# KMO_IO_MV9.net
KiCad netlist of a schematic drawn in EAGLE
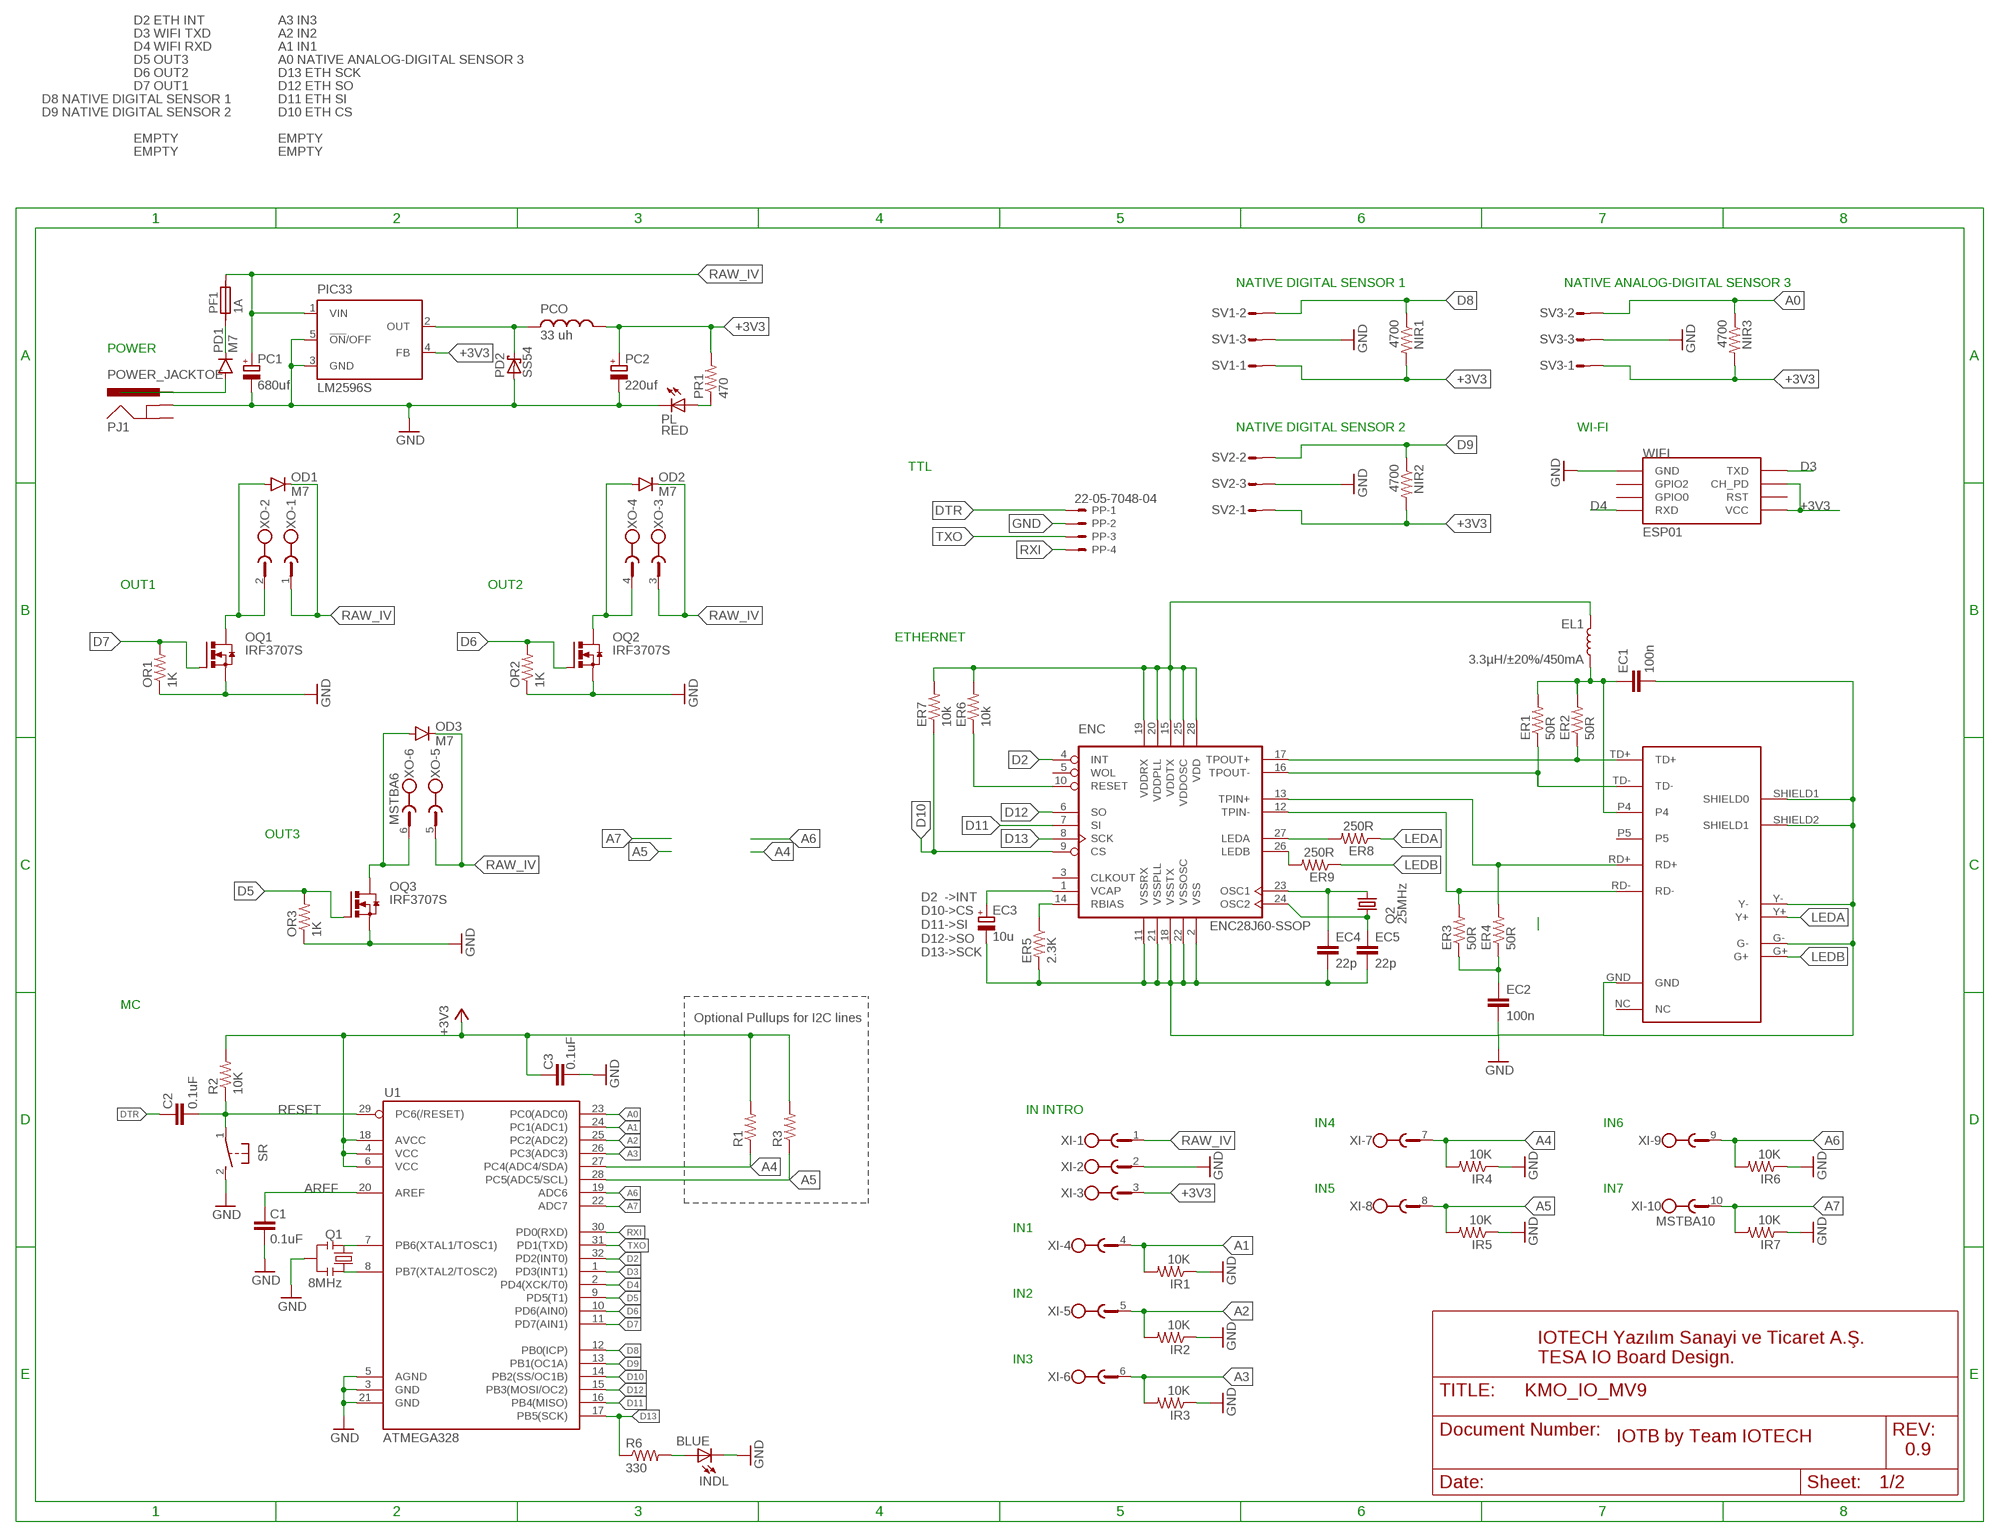
[diagram p0: schematic, sheet 1]
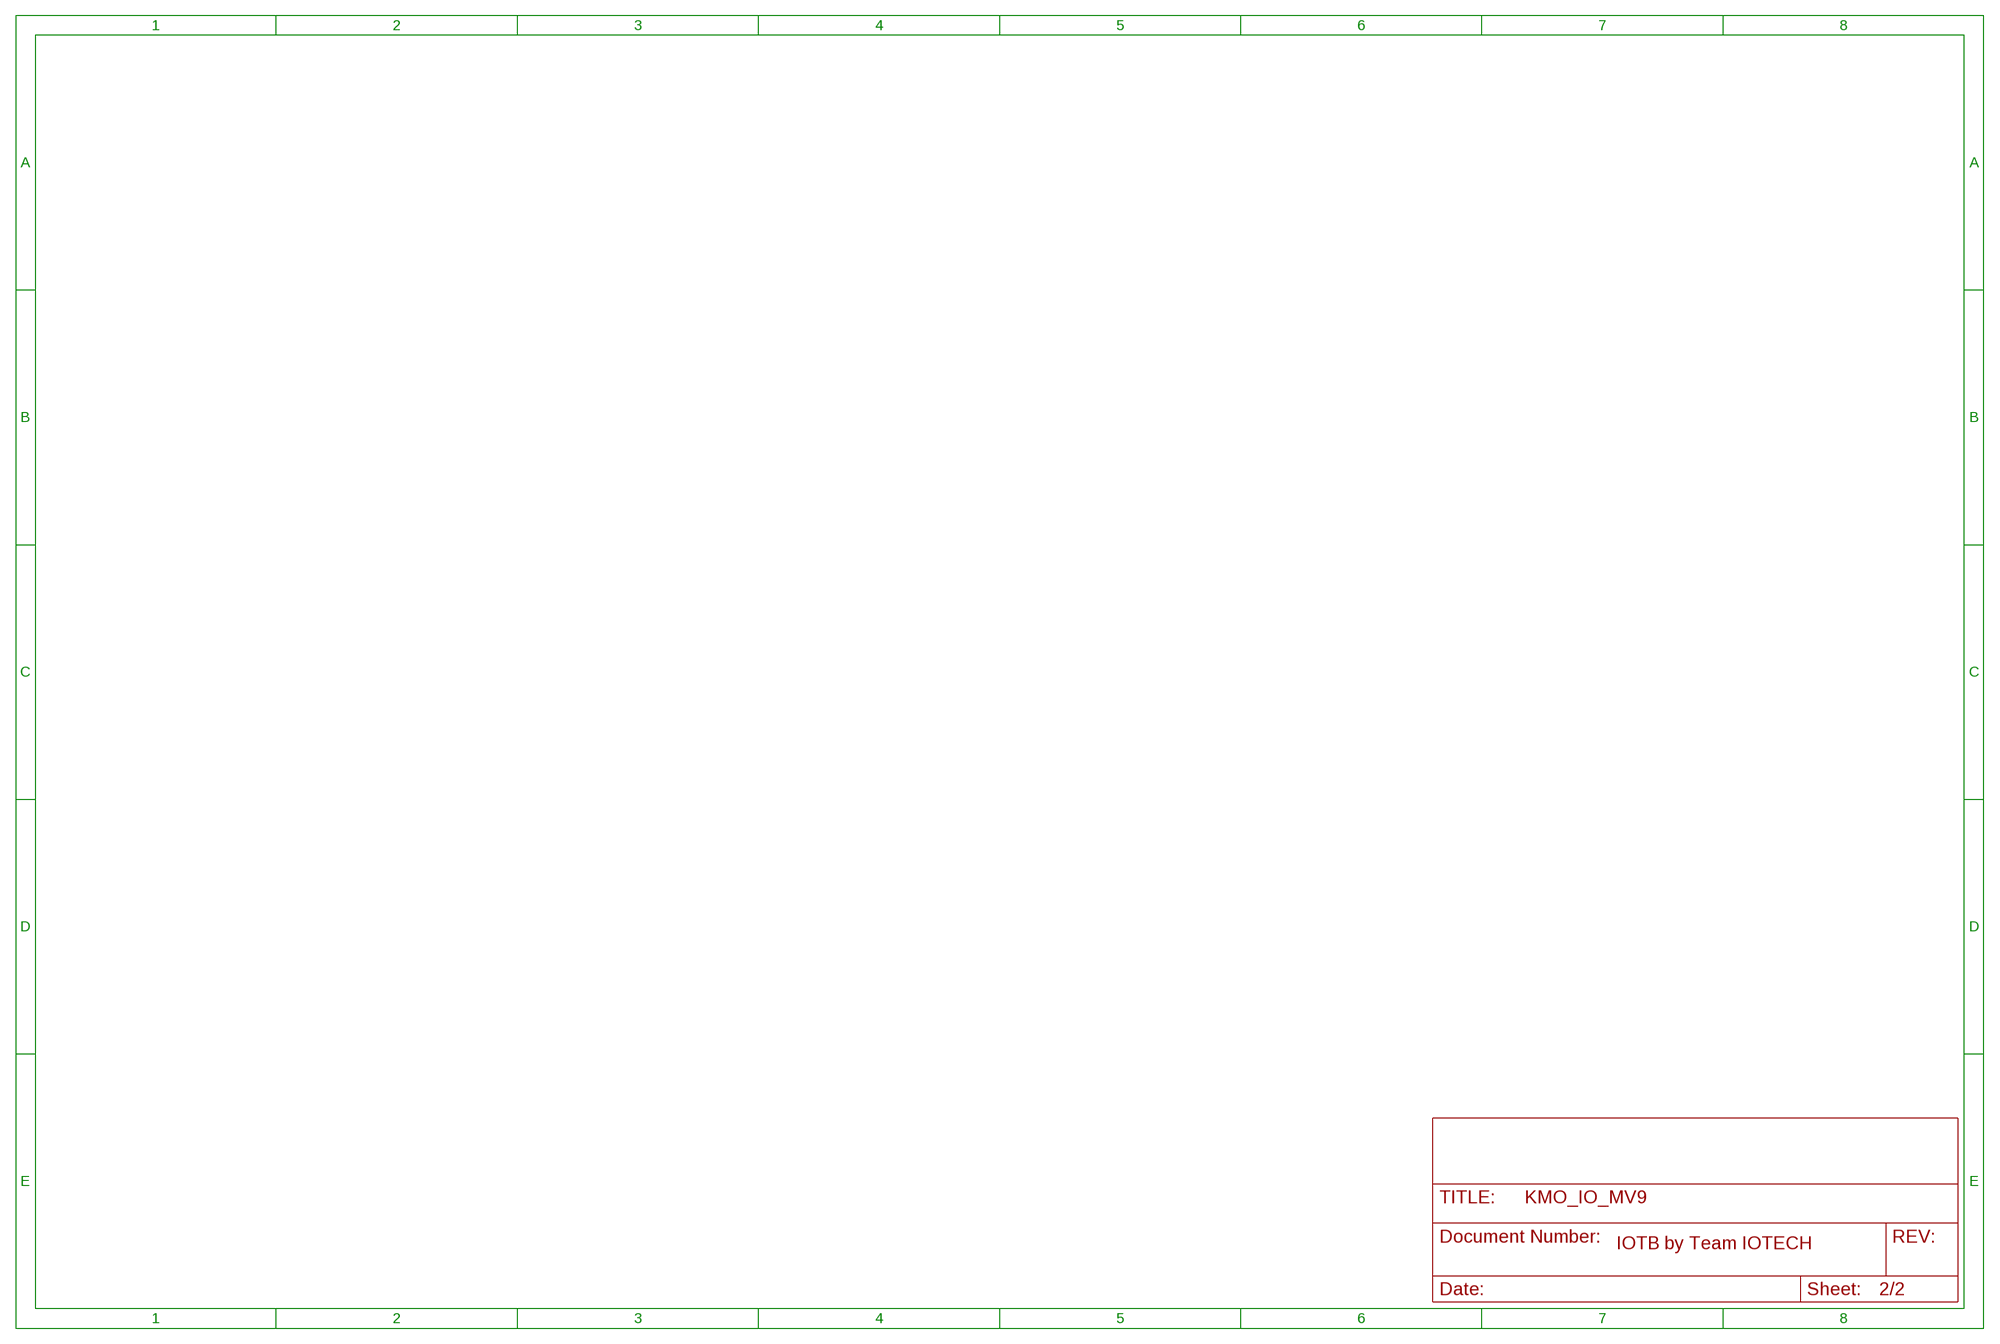
[diagram p1: schematic, sheet 2]

(export (version "E")
  (design (tool "Eeschema 10.0.6"))
  (components
    (comp (ref "C1")
      (value "0.1uF")
      (footprint "eagle-import:0805")
      (libsource (lib "eagle-import") (part "CAP0805"))
    )
    (comp (ref "C2")
      (value "0.1uF")
      (footprint "eagle-import:0805")
      (libsource (lib "eagle-import") (part "CAP0805"))
    )
    (comp (ref "C3")
      (value "0.1uF")
      (footprint "eagle-import:0805")
      (libsource (lib "eagle-import") (part "CAP0805"))
    )
    (comp (ref "EC1")
      (value "100n")
      (footprint "eagle-import:0805")
      (libsource (lib "eagle-import") (part "CAP0805"))
    )
    (comp (ref "EC2")
      (value "100n")
      (footprint "eagle-import:0805")
      (libsource (lib "eagle-import") (part "CAP0805"))
    )
    (comp (ref "EC3")
      (value "10u")
      (footprint "eagle-import:CT3216")
      (libsource (lib "eagle-import") (part "CPOL-EUCT3216"))
    )
    (comp (ref "EC4")
      (value "22p")
      (footprint "eagle-import:0805")
      (libsource (lib "eagle-import") (part "CAP0805"))
    )
    (comp (ref "EC5")
      (value "22p")
      (footprint "eagle-import:0805")
      (libsource (lib "eagle-import") (part "CAP0805"))
    )
    (comp (ref "EL1")
      (value "3.3µH/±20%/450mA")
      (footprint "eagle-import:0805")
      (libsource (lib "eagle-import") (part "INDUCTOR-0805-3.3UH"))
    )
    (comp (ref "ENC")
      (value "ENC28J60-SSOP")
      (footprint "eagle-import:SSOP28")
      (libsource (lib "eagle-import") (part "ENC28J60-SSOP"))
    )
    (comp (ref "ER1")
      (value "50R")
      (footprint "eagle-import:0805")
      (libsource (lib "eagle-import") (part "RESISTOR0805-RES"))
    )
    (comp (ref "ER2")
      (value "50R")
      (footprint "eagle-import:0805")
      (libsource (lib "eagle-import") (part "RESISTOR0805-RES"))
    )
    (comp (ref "ER3")
      (value "50R")
      (footprint "eagle-import:0805")
      (libsource (lib "eagle-import") (part "RESISTOR0805-RES"))
    )
    (comp (ref "ER4")
      (value "50R")
      (footprint "eagle-import:0805")
      (libsource (lib "eagle-import") (part "RESISTOR0805-RES"))
    )
    (comp (ref "ER5")
      (value "2.3K")
      (footprint "eagle-import:0805")
      (libsource (lib "eagle-import") (part "RESISTOR0805-RES"))
    )
    (comp (ref "ER6")
      (value "10k")
      (footprint "eagle-import:0805")
      (libsource (lib "eagle-import") (part "RESISTOR0805-RES"))
    )
    (comp (ref "ER7")
      (value "10k")
      (footprint "eagle-import:0805")
      (libsource (lib "eagle-import") (part "RESISTOR0805-RES"))
    )
    (comp (ref "ER8")
      (value "250R")
      (footprint "eagle-import:0805")
      (libsource (lib "eagle-import") (part "RESISTOR0805-RES"))
    )
    (comp (ref "ER9")
      (value "250R")
      (footprint "eagle-import:0805")
      (libsource (lib "eagle-import") (part "RESISTOR0805-RES"))
    )
    (comp (ref "INDL")
      (value "BLUE")
      (footprint "eagle-import:CHIP-LED0805")
      (libsource (lib "eagle-import") (part "LEDCHIP-LED0805"))
    )
    (comp (ref "IR1")
      (value "10K")
      (footprint "eagle-import:0805")
      (libsource (lib "eagle-import") (part "RESISTOR0805-RES"))
    )
    (comp (ref "IR2")
      (value "10K")
      (footprint "eagle-import:0805")
      (libsource (lib "eagle-import") (part "RESISTOR0805-RES"))
    )
    (comp (ref "IR3")
      (value "10K")
      (footprint "eagle-import:0805")
      (libsource (lib "eagle-import") (part "RESISTOR0805-RES"))
    )
    (comp (ref "IR4")
      (value "10K")
      (footprint "eagle-import:0805")
      (libsource (lib "eagle-import") (part "RESISTOR0805-RES"))
    )
    (comp (ref "IR5")
      (value "10K")
      (footprint "eagle-import:0805")
      (libsource (lib "eagle-import") (part "RESISTOR0805-RES"))
    )
    (comp (ref "IR6")
      (value "10K")
      (footprint "eagle-import:0805")
      (libsource (lib "eagle-import") (part "RESISTOR0805-RES"))
    )
    (comp (ref "IR7")
      (value "10K")
      (footprint "eagle-import:0805")
      (libsource (lib "eagle-import") (part "RESISTOR0805-RES"))
    )
    (comp (ref "NIR1")
      (value "4700")
      (footprint "eagle-import:0805")
      (libsource (lib "eagle-import") (part "RESISTOR0805-RES"))
    )
    (comp (ref "NIR2")
      (value "4700")
      (footprint "eagle-import:0805")
      (libsource (lib "eagle-import") (part "RESISTOR0805-RES"))
    )
    (comp (ref "NIR3")
      (value "4700")
      (footprint "eagle-import:0805")
      (libsource (lib "eagle-import") (part "RESISTOR0805-RES"))
    )
    (comp (ref "OD1")
      (value "M7")
      (footprint "eagle-import:SMA-DIODE")
      (libsource (lib "eagle-import") (part "DIODESMA"))
    )
    (comp (ref "OD2")
      (value "M7")
      (footprint "eagle-import:SMA-DIODE")
      (libsource (lib "eagle-import") (part "DIODESMA"))
    )
    (comp (ref "OD3")
      (value "M7")
      (footprint "eagle-import:SMA-DIODE")
      (libsource (lib "eagle-import") (part "DIODESMA"))
    )
    (comp (ref "OQ1")
      (value "IRF3707S")
      (footprint "eagle-import:D2PACK")
      (libsource (lib "eagle-import") (part "IRF3704S"))
    )
    (comp (ref "OQ2")
      (value "IRF3707S")
      (footprint "eagle-import:D2PACK")
      (libsource (lib "eagle-import") (part "IRF3704S"))
    )
    (comp (ref "OQ3")
      (value "IRF3707S")
      (footprint "eagle-import:D2PACK")
      (libsource (lib "eagle-import") (part "IRF3704S"))
    )
    (comp (ref "OR1")
      (value "1K")
      (footprint "eagle-import:0805")
      (libsource (lib "eagle-import") (part "RESISTOR0805-RES"))
    )
    (comp (ref "OR2")
      (value "1K")
      (footprint "eagle-import:0805")
      (libsource (lib "eagle-import") (part "RESISTOR0805-RES"))
    )
    (comp (ref "OR3")
      (value "1K")
      (footprint "eagle-import:0805")
      (libsource (lib "eagle-import") (part "RESISTOR0805-RES"))
    )
    (comp (ref "PC1")
      (value "680uf")
      (footprint "eagle-import:140CLH-1010")
      (libsource (lib "eagle-import") (part "CPOL-EU140CLH-1010"))
    )
    (comp (ref "PC2")
      (value "220uf")
      (footprint "eagle-import:140CLH-1010")
      (libsource (lib "eagle-import") (part "CPOL-EU140CLH-1010"))
    )
    (comp (ref "PCO")
      (value "33 uh")
      (footprint "eagle-import:MSS1260")
      (libsource (lib "eagle-import") (part "MSS1260"))
    )
    (comp (ref "PD1")
      (value "M7")
      (footprint "eagle-import:SMA-DIODE")
      (libsource (lib "eagle-import") (part "DIODESMA"))
    )
    (comp (ref "PD2")
      (value "SS54")
      (footprint "eagle-import:SMB")
      (libsource (lib "eagle-import") (part "SCHOTTKY-DIODESMD"))
    )
    (comp (ref "PF1")
      (value "1A")
      (footprint "eagle-import:1820")
      (libsource (lib "eagle-import") (part "SIBA194600"))
    )
    (comp (ref "PIC33")
      (value "LM2596S")
      (footprint "eagle-import:TO263-5")
      (fields (field (name "MF") "NATIONAL SEMICONDUCTOR") (field (name "MPN") "LM2596S-ADJ/NOPB"))
      (libsource (lib "eagle-import") (part "LM2596S"))
    )
    (comp (ref "PJ1")
      (value "POWER_JACKTOE")
      (footprint "eagle-import:POWER_JACK_SMD_OVERPASTE_TOE")
      (libsource (lib "eagle-import") (part "POWER_JACKTOE"))
    )
    (comp (ref "PL")
      (value "RED")
      (footprint "eagle-import:CHIP-LED0805")
      (libsource (lib "eagle-import") (part "LEDCHIP-LED0805"))
    )
    (comp (ref "PP")
      (value "22-05-7048-04")
      (footprint "eagle-import:7395-04")
      (fields (field (name "MF") "MOLEX"))
      (libsource (lib "eagle-import") (part "22-?-0405-7048"))
    )
    (comp (ref "PR1")
      (value "470")
      (footprint "eagle-import:0805")
      (libsource (lib "eagle-import") (part "RESISTOR0805-RES"))
    )
    (comp (ref "Q1")
      (value "8MHz")
      (footprint "eagle-import:RESONATOR-SMD-1_1")
      (libsource (lib "eagle-import") (part "RESONATOR1{colon}1"))
    )
    (comp (ref "Q2")
      (value "25MHz")
      (footprint "eagle-import:5.0X3.2_2")
      (libsource (lib "eagle-import") (part "KX-9B"))
    )
    (comp (ref "R1")
      (value "RESISTOR0805-RES")
      (footprint "eagle-import:0805")
      (libsource (lib "eagle-import") (part "RESISTOR0805-RES"))
    )
    (comp (ref "R2")
      (value "10K")
      (footprint "eagle-import:0805")
      (libsource (lib "eagle-import") (part "RESISTOR0805-RES"))
    )
    (comp (ref "R3")
      (value "RESISTOR0805-RES")
      (footprint "eagle-import:0805")
      (libsource (lib "eagle-import") (part "RESISTOR0805-RES"))
    )
    (comp (ref "R6")
      (value "330")
      (footprint "eagle-import:0805")
      (libsource (lib "eagle-import") (part "RESISTOR0805-RES"))
    )
    (comp (ref "SR")
      (value "31-XX")
      (footprint "eagle-import:B3F-31XX")
      (fields (field (name "MPN") "B3F-3100"))
      (libsource (lib "eagle-import") (part "31-XX"))
    )
    (comp (ref "SV1")
      (value "S03P")
      (footprint "eagle-import:S03P")
      (libsource (lib "eagle-import") (part "S03P"))
    )
    (comp (ref "SV2")
      (value "S03P")
      (footprint "eagle-import:S03P")
      (libsource (lib "eagle-import") (part "S03P"))
    )
    (comp (ref "SV3")
      (value "S03P")
      (footprint "eagle-import:S03P")
      (libsource (lib "eagle-import") (part "S03P"))
    )
    (comp (ref "U$2")
      (value "HR911105A")
      (footprint "eagle-import:RJ45")
      (libsource (lib "eagle-import") (part "HR911105A"))
    )
    (comp (ref "U1")
      (value "ATMEGA328")
      (footprint "eagle-import:TQFP32-08")
      (libsource (lib "eagle-import") (part "ATMEGA168"))
    )
    (comp (ref "WIFI")
      (value "ESP01")
      (footprint "eagle-import:ESP01")
      (libsource (lib "eagle-import") (part "ESP01"))
    )
    (comp (ref "XI")
      (value "MSTBA10")
      (footprint "eagle-import:MSTBA10")
      (fields (field (name "MF") "FARNELL") (field (name "MPN") "1757323"))
      (libsource (lib "eagle-import") (part "MSTBA10"))
    )
    (comp (ref "XO")
      (value "MSTBA6")
      (footprint "eagle-import:MSTBA6")
      (fields (field (name "MF") "FARNELL") (field (name "MPN") "1757284"))
      (libsource (lib "eagle-import") (part "MSTBA6"))
    )
  )
  (nets
    (net (code "1") (name "+3V3") (class "Default")
      (node (ref "C3") (pin "2") (pinfunction "2_2") (pintype "passive"))
      (node (ref "EL1") (pin "1") (pinfunction "1_1") (pintype "passive"))
      (node (ref "ENC") (pin "15") (pinfunction "VDDTX_15") (pintype "power_in"))
      (node (ref "ENC") (pin "19") (pinfunction "VDDRX_19") (pintype "power_in"))
      (node (ref "ENC") (pin "20") (pinfunction "VDDPLL_20") (pintype "power_in"))
      (node (ref "ENC") (pin "25") (pinfunction "VDDOSC_25") (pintype "power_in"))
      (node (ref "ENC") (pin "28") (pinfunction "VDD_28") (pintype "power_in"))
      (node (ref "ER6") (pin "2") (pinfunction "2_2") (pintype "passive"))
      (node (ref "ER7") (pin "2") (pinfunction "2_2") (pintype "passive"))
      (node (ref "NIR1") (pin "2") (pinfunction "2_2") (pintype "passive"))
      (node (ref "NIR2") (pin "2") (pinfunction "2_2") (pintype "passive"))
      (node (ref "NIR3") (pin "2") (pinfunction "2_2") (pintype "passive"))
      (node (ref "PC2") (pin "+") (pinfunction "+_+") (pintype "passive"))
      (node (ref "PCO") (pin "P$1") (pinfunction "P$1_P$1") (pintype "passive"))
      (node (ref "PIC33") (pin "4") (pinfunction "FB_4") (pintype "input"))
      (node (ref "PR1") (pin "2") (pinfunction "2_2") (pintype "passive"))
      (node (ref "R1") (pin "2") (pinfunction "2_2") (pintype "passive"))
      (node (ref "R2") (pin "2") (pinfunction "2_2") (pintype "passive"))
      (node (ref "R3") (pin "2") (pinfunction "2_2") (pintype "passive"))
      (node (ref "SV1") (pin "1") (pinfunction "S_1") (pintype "passive"))
      (node (ref "SV2") (pin "1") (pinfunction "S_1") (pintype "passive"))
      (node (ref "SV3") (pin "1") (pinfunction "S_1") (pintype "passive"))
      (node (ref "U1") (pin "18") (pinfunction "AVCC_18") (pintype "bidirectional"))
      (node (ref "U1") (pin "4") (pinfunction "VCC_4") (pintype "bidirectional"))
      (node (ref "U1") (pin "6") (pinfunction "VCC_6") (pintype "bidirectional"))
      (node (ref "WIFI") (pin "CH_PD") (pinfunction "CH_PD_CH_PD") (pintype "bidirectional"))
      (node (ref "WIFI") (pin "VCC") (pinfunction "VCC_VCC") (pintype "bidirectional"))
      (node (ref "XI") (pin "3") (pinfunction "1_3") (pintype "passive"))
    )
    (net (code "2") (name "A0") (class "Default")
      (node (ref "NIR3") (pin "1") (pinfunction "1_1") (pintype "passive"))
      (node (ref "SV3") (pin "2") (pinfunction "S_2") (pintype "passive"))
      (node (ref "U1") (pin "23") (pinfunction "PC0(ADC0)_23") (pintype "bidirectional"))
    )
    (net (code "3") (name "A1") (class "Default")
      (node (ref "IR1") (pin "2") (pinfunction "2_2") (pintype "passive"))
      (node (ref "U1") (pin "24") (pinfunction "PC1(ADC1)_24") (pintype "bidirectional"))
      (node (ref "XI") (pin "4") (pinfunction "1_4") (pintype "passive"))
    )
    (net (code "4") (name "A2") (class "Default")
      (node (ref "IR2") (pin "2") (pinfunction "2_2") (pintype "passive"))
      (node (ref "U1") (pin "25") (pinfunction "PC2(ADC2)_25") (pintype "bidirectional"))
      (node (ref "XI") (pin "5") (pinfunction "1_5") (pintype "passive"))
    )
    (net (code "5") (name "A3") (class "Default")
      (node (ref "IR3") (pin "2") (pinfunction "2_2") (pintype "passive"))
      (node (ref "U1") (pin "26") (pinfunction "PC3(ADC3)_26") (pintype "bidirectional"))
      (node (ref "XI") (pin "6") (pinfunction "1_6") (pintype "passive"))
    )
    (net (code "6") (name "A4") (class "Default")
      (node (ref "IR4") (pin "2") (pinfunction "2_2") (pintype "passive"))
      (node (ref "R1") (pin "1") (pinfunction "1_1") (pintype "passive"))
      (node (ref "U1") (pin "27") (pinfunction "PC4(ADC4/SDA)_27") (pintype "bidirectional"))
      (node (ref "XI") (pin "7") (pinfunction "1_7") (pintype "passive"))
    )
    (net (code "7") (name "A5") (class "Default")
      (node (ref "IR5") (pin "2") (pinfunction "2_2") (pintype "passive"))
      (node (ref "R3") (pin "1") (pinfunction "1_1") (pintype "passive"))
      (node (ref "U1") (pin "28") (pinfunction "PC5(ADC5/SCL)_28") (pintype "bidirectional"))
      (node (ref "XI") (pin "8") (pinfunction "1_8") (pintype "passive"))
    )
    (net (code "8") (name "A6") (class "Default")
      (node (ref "IR6") (pin "2") (pinfunction "2_2") (pintype "passive"))
      (node (ref "U1") (pin "19") (pinfunction "ADC6_19") (pintype "bidirectional"))
      (node (ref "XI") (pin "9") (pinfunction "1_9") (pintype "passive"))
    )
    (net (code "9") (name "A7") (class "Default")
      (node (ref "IR7") (pin "2") (pinfunction "2_2") (pintype "passive"))
      (node (ref "U1") (pin "22") (pinfunction "ADC7_22") (pintype "bidirectional"))
      (node (ref "XI") (pin "10") (pinfunction "1_10") (pintype "passive"))
    )
    (net (code "10") (name "AREF") (class "Default")
      (node (ref "C1") (pin "2") (pinfunction "2_2") (pintype "passive"))
      (node (ref "U1") (pin "20") (pinfunction "AREF_20") (pintype "bidirectional"))
    )
    (net (code "11") (name "D2") (class "Default")
      (node (ref "ENC") (pin "4") (pinfunction "INT_4") (pintype "output"))
      (node (ref "U1") (pin "32") (pinfunction "PD2(INT0)_32") (pintype "bidirectional"))
    )
    (net (code "12") (name "D3") (class "Default")
      (node (ref "U1") (pin "1") (pinfunction "PD3(INT1)_1") (pintype "bidirectional"))
      (node (ref "WIFI") (pin "TX") (pinfunction "TXD_TX") (pintype "bidirectional"))
    )
    (net (code "13") (name "D4") (class "Default")
      (node (ref "U1") (pin "2") (pinfunction "PD4(XCK/T0)_2") (pintype "bidirectional"))
      (node (ref "WIFI") (pin "RX") (pinfunction "RXD_RX") (pintype "bidirectional"))
    )
    (net (code "14") (name "D5") (class "Default")
      (node (ref "OQ3") (pin "1") (pinfunction "G_1") (pintype "passive"))
      (node (ref "OR3") (pin "2") (pinfunction "2_2") (pintype "passive"))
      (node (ref "U1") (pin "9") (pinfunction "PD5(T1)_9") (pintype "bidirectional"))
    )
    (net (code "15") (name "D6") (class "Default")
      (node (ref "OQ2") (pin "1") (pinfunction "G_1") (pintype "passive"))
      (node (ref "OR2") (pin "2") (pinfunction "2_2") (pintype "passive"))
      (node (ref "U1") (pin "10") (pinfunction "PD6(AIN0)_10") (pintype "bidirectional"))
    )
    (net (code "16") (name "D7") (class "Default")
      (node (ref "OQ1") (pin "1") (pinfunction "G_1") (pintype "passive"))
      (node (ref "OR1") (pin "2") (pinfunction "2_2") (pintype "passive"))
      (node (ref "U1") (pin "11") (pinfunction "PD7(AIN1)_11") (pintype "bidirectional"))
    )
    (net (code "17") (name "D8") (class "Default")
      (node (ref "NIR1") (pin "1") (pinfunction "1_1") (pintype "passive"))
      (node (ref "SV1") (pin "2") (pinfunction "S_2") (pintype "passive"))
      (node (ref "U1") (pin "12") (pinfunction "PB0(ICP)_12") (pintype "bidirectional"))
    )
    (net (code "18") (name "D9") (class "Default")
      (node (ref "NIR2") (pin "1") (pinfunction "1_1") (pintype "passive"))
      (node (ref "SV2") (pin "2") (pinfunction "S_2") (pintype "passive"))
      (node (ref "U1") (pin "13") (pinfunction "PB1(OC1A)_13") (pintype "bidirectional"))
    )
    (net (code "19") (name "D10") (class "Default")
      (node (ref "ENC") (pin "9") (pinfunction "CS_9") (pintype "input"))
      (node (ref "ER7") (pin "1") (pinfunction "1_1") (pintype "passive"))
      (node (ref "U1") (pin "14") (pinfunction "PB2(SS/OC1B)_14") (pintype "bidirectional"))
    )
    (net (code "20") (name "D11") (class "Default")
      (node (ref "ENC") (pin "7") (pinfunction "SI_7") (pintype "input"))
      (node (ref "U1") (pin "16") (pinfunction "PB4(MISO)_16") (pintype "bidirectional"))
    )
    (net (code "21") (name "D12") (class "Default")
      (node (ref "ENC") (pin "6") (pinfunction "SO_6") (pintype "output"))
      (node (ref "U1") (pin "15") (pinfunction "PB3(MOSI/OC2)_15") (pintype "bidirectional"))
    )
    (net (code "22") (name "D13") (class "Default")
      (node (ref "ENC") (pin "8") (pinfunction "SCK_8") (pintype "input"))
      (node (ref "R6") (pin "1") (pinfunction "1_1") (pintype "passive"))
      (node (ref "U1") (pin "17") (pinfunction "PB5(SCK)_17") (pintype "bidirectional"))
    )
    (net (code "23") (name "DTR") (class "Default")
      (node (ref "C2") (pin "2") (pinfunction "2_2") (pintype "passive"))
      (node (ref "PP") (pin "1") (pinfunction "S_1") (pintype "passive"))
    )
    (net (code "24") (name "GND") (class "Default")
      (node (ref "C1") (pin "1") (pinfunction "1_1") (pintype "passive"))
      (node (ref "C3") (pin "1") (pinfunction "1_1") (pintype "passive"))
      (node (ref "EC1") (pin "2") (pinfunction "2_2") (pintype "passive"))
      (node (ref "EC2") (pin "2") (pinfunction "2_2") (pintype "passive"))
      (node (ref "EC3") (pin "-") (pinfunction "-_-") (pintype "passive"))
      (node (ref "EC4") (pin "2") (pinfunction "2_2") (pintype "passive"))
      (node (ref "EC5") (pin "2") (pinfunction "2_2") (pintype "passive"))
      (node (ref "ENC") (pin "11") (pinfunction "VSSRX_11") (pintype "power_in"))
      (node (ref "ENC") (pin "18") (pinfunction "VSSTX_18") (pintype "power_in"))
      (node (ref "ENC") (pin "2") (pinfunction "VSS_2") (pintype "power_in"))
      (node (ref "ENC") (pin "21") (pinfunction "VSSPLL_21") (pintype "power_in"))
      (node (ref "ENC") (pin "22") (pinfunction "VSSOSC_22") (pintype "power_in"))
      (node (ref "ER5") (pin "2") (pinfunction "2_2") (pintype "passive"))
      (node (ref "INDL") (pin "C") (pinfunction "C_C") (pintype "passive"))
      (node (ref "IR1") (pin "1") (pinfunction "1_1") (pintype "passive"))
      (node (ref "IR2") (pin "1") (pinfunction "1_1") (pintype "passive"))
      (node (ref "IR3") (pin "1") (pinfunction "1_1") (pintype "passive"))
      (node (ref "IR4") (pin "1") (pinfunction "1_1") (pintype "passive"))
      (node (ref "IR5") (pin "1") (pinfunction "1_1") (pintype "passive"))
      (node (ref "IR6") (pin "1") (pinfunction "1_1") (pintype "passive"))
      (node (ref "IR7") (pin "1") (pinfunction "1_1") (pintype "passive"))
      (node (ref "OQ1") (pin "3") (pinfunction "S_3") (pintype "passive"))
      (node (ref "OQ2") (pin "3") (pinfunction "S_3") (pintype "passive"))
      (node (ref "OQ3") (pin "3") (pinfunction "S_3") (pintype "passive"))
      (node (ref "OR1") (pin "1") (pinfunction "1_1") (pintype "passive"))
      (node (ref "OR2") (pin "1") (pinfunction "1_1") (pintype "passive"))
      (node (ref "OR3") (pin "1") (pinfunction "1_1") (pintype "passive"))
      (node (ref "PC1") (pin "-") (pinfunction "-_-") (pintype "passive"))
      (node (ref "PC2") (pin "-") (pinfunction "-_-") (pintype "passive"))
      (node (ref "PD2") (pin "A") (pinfunction "A_A") (pintype "passive"))
      (node (ref "PIC33") (pin "3") (pinfunction "GND_3") (pintype "power_in"))
      (node (ref "PIC33") (pin "5") (pinfunction "~{ON}/OFF_5") (pintype "input"))
      (node (ref "PJ1") (pin "GND") (pinfunction "GNDBREAK_GND") (pintype "bidirectional"))
      (node (ref "PL") (pin "C") (pinfunction "C_C") (pintype "passive"))
      (node (ref "PP") (pin "2") (pinfunction "S_2") (pintype "passive"))
      (node (ref "Q1") (pin "2") (pinfunction "2_2") (pintype "passive"))
      (node (ref "SR") (pin "2") (pinfunction "S_2") (pintype "passive"))
      (node (ref "SV1") (pin "3") (pinfunction "S_3") (pintype "passive"))
      (node (ref "SV2") (pin "3") (pinfunction "S_3") (pintype "passive"))
      (node (ref "SV3") (pin "3") (pinfunction "S_3") (pintype "passive"))
      (node (ref "U$2") (pin "G-") (pinfunction "G-_G-") (pintype "bidirectional"))
      (node (ref "U$2") (pin "GND") (pinfunction "GND_GND") (pintype "bidirectional"))
      (node (ref "U$2") (pin "SHIELD1") (pinfunction "SHIELD0_SHIELD1") (pintype "bidirectional"))
      (node (ref "U$2") (pin "SHIELD2") (pinfunction "SHIELD1_SHIELD2") (pintype "bidirectional"))
      (node (ref "U$2") (pin "Y-") (pinfunction "Y-_Y-") (pintype "bidirectional"))
      (node (ref "U1") (pin "21") (pinfunction "GND_21") (pintype "bidirectional"))
      (node (ref "U1") (pin "3") (pinfunction "GND_3") (pintype "bidirectional"))
      (node (ref "U1") (pin "5") (pinfunction "AGND_5") (pintype "bidirectional"))
      (node (ref "WIFI") (pin "GND") (pinfunction "GND_GND") (pintype "bidirectional"))
      (node (ref "XI") (pin "2") (pinfunction "1_2") (pintype "passive"))
    )
    (net (code "25") (name "LEDA") (class "Default")
      (node (ref "ER8") (pin "1") (pinfunction "1_1") (pintype "passive"))
      (node (ref "U$2") (pin "Y+") (pinfunction "Y+_Y+") (pintype "bidirectional"))
    )
    (net (code "26") (name "LEDB") (class "Default")
      (node (ref "ER9") (pin "1") (pinfunction "1_1") (pintype "passive"))
      (node (ref "U$2") (pin "G+") (pinfunction "G+_G+") (pintype "bidirectional"))
    )
    (net (code "27") (name "Net-(EC1-Pad1)") (class "Default")
      (node (ref "EC1") (pin "1") (pinfunction "1_1") (pintype "passive"))
      (node (ref "EL1") (pin "2") (pinfunction "2_2") (pintype "passive"))
      (node (ref "ER1") (pin "2") (pinfunction "2_2") (pintype "passive"))
      (node (ref "ER2") (pin "2") (pinfunction "2_2") (pintype "passive"))
      (node (ref "U$2") (pin "P4") (pinfunction "P4_P4") (pintype "bidirectional"))
    )
    (net (code "28") (name "Net-(EC2-Pad1)") (class "Default")
      (node (ref "EC2") (pin "1") (pinfunction "1_1") (pintype "passive"))
      (node (ref "ER3") (pin "1") (pinfunction "1_1") (pintype "passive"))
      (node (ref "ER4") (pin "1") (pinfunction "1_1") (pintype "passive"))
    )
    (net (code "29") (name "Net-(ENC-LEDA)") (class "Default")
      (node (ref "ENC") (pin "27") (pinfunction "LEDA_27") (pintype "output"))
      (node (ref "ER8") (pin "2") (pinfunction "2_2") (pintype "passive"))
    )
    (net (code "30") (name "Net-(ENC-LEDB)") (class "Default")
      (node (ref "ENC") (pin "26") (pinfunction "LEDB_26") (pintype "output"))
      (node (ref "ER9") (pin "2") (pinfunction "2_2") (pintype "passive"))
    )
    (net (code "31") (name "Net-(ENC-OSC1)") (class "Default")
      (node (ref "EC4") (pin "1") (pinfunction "1_1") (pintype "passive"))
      (node (ref "ENC") (pin "23") (pinfunction "OSC1_23") (pintype "input"))
      (node (ref "Q2") (pin "2") (pinfunction "2_2") (pintype "passive"))
    )
    (net (code "32") (name "Net-(ENC-OSC2)") (class "Default")
      (node (ref "EC5") (pin "1") (pinfunction "1_1") (pintype "passive"))
      (node (ref "ENC") (pin "24") (pinfunction "OSC2_24") (pintype "output"))
      (node (ref "Q2") (pin "1") (pinfunction "1_1") (pintype "passive"))
    )
    (net (code "33") (name "Net-(ENC-RBIAS)") (class "Default")
      (node (ref "ENC") (pin "14") (pinfunction "RBIAS_14") (pintype "passive"))
      (node (ref "ER5") (pin "1") (pinfunction "1_1") (pintype "passive"))
    )
    (net (code "34") (name "Net-(ENC-RESET)") (class "Default")
      (node (ref "ENC") (pin "10") (pinfunction "RESET_10") (pintype "input"))
      (node (ref "ER6") (pin "1") (pinfunction "1_1") (pintype "passive"))
    )
    (net (code "35") (name "Net-(ENC-TPIN+)") (class "Default")
      (node (ref "ENC") (pin "13") (pinfunction "TPIN+_13") (pintype "input"))
      (node (ref "ER4") (pin "2") (pinfunction "2_2") (pintype "passive"))
      (node (ref "U$2") (pin "RD+") (pinfunction "RD+_RD+") (pintype "bidirectional"))
    )
    (net (code "36") (name "Net-(ENC-TPIN-)") (class "Default")
      (node (ref "ENC") (pin "12") (pinfunction "TPIN-_12") (pintype "input"))
      (node (ref "ER3") (pin "2") (pinfunction "2_2") (pintype "passive"))
      (node (ref "U$2") (pin "RD-") (pinfunction "RD-_RD-") (pintype "bidirectional"))
    )
    (net (code "37") (name "Net-(ENC-TPOUT+)") (class "Default")
      (node (ref "ENC") (pin "17") (pinfunction "TPOUT+_17") (pintype "output"))
      (node (ref "ER2") (pin "1") (pinfunction "1_1") (pintype "passive"))
      (node (ref "U$2") (pin "TD+") (pinfunction "TD+_TD+") (pintype "bidirectional"))
    )
    (net (code "38") (name "Net-(ENC-TPOUT-)") (class "Default")
      (node (ref "ENC") (pin "16") (pinfunction "TPOUT-_16") (pintype "output"))
      (node (ref "ER1") (pin "1") (pinfunction "1_1") (pintype "passive"))
      (node (ref "U$2") (pin "TD-") (pinfunction "TD-_TD-") (pintype "bidirectional"))
    )
    (net (code "39") (name "Net-(ENC-VCAP)") (class "Default")
      (node (ref "EC3") (pin "+") (pinfunction "+_+") (pintype "passive"))
      (node (ref "ENC") (pin "1") (pinfunction "VCAP_1") (pintype "power_in"))
    )
    (net (code "40") (name "Net-(INDL-PadA)") (class "Default")
      (node (ref "INDL") (pin "A") (pinfunction "A_A") (pintype "passive"))
      (node (ref "R6") (pin "2") (pinfunction "2_2") (pintype "passive"))
    )
    (net (code "41") (name "Net-(OQ1-D)") (class "Default")
      (node (ref "OD1") (pin "A") (pinfunction "A_A") (pintype "passive"))
      (node (ref "OQ1") (pin "2") (pinfunction "D_2") (pintype "passive"))
      (node (ref "XO") (pin "2") (pinfunction "1_2") (pintype "passive"))
    )
    (net (code "42") (name "Net-(OQ2-D)") (class "Default")
      (node (ref "OD2") (pin "A") (pinfunction "A_A") (pintype "passive"))
      (node (ref "OQ2") (pin "2") (pinfunction "D_2") (pintype "passive"))
      (node (ref "XO") (pin "4") (pinfunction "1_4") (pintype "passive"))
    )
    (net (code "43") (name "Net-(OQ3-D)") (class "Default")
      (node (ref "OD3") (pin "A") (pinfunction "A_A") (pintype "passive"))
      (node (ref "OQ3") (pin "2") (pinfunction "D_2") (pintype "passive"))
      (node (ref "XO") (pin "6") (pinfunction "1_6") (pintype "passive"))
    )
    (net (code "44") (name "Net-(PD1-PadC)") (class "Default")
      (node (ref "PD1") (pin "C") (pinfunction "C_C") (pintype "passive"))
      (node (ref "PF1") (pin "1") (pinfunction "1_1") (pintype "passive"))
    )
    (net (code "45") (name "Net-(PIC33-OUT)") (class "Default")
      (node (ref "PCO") (pin "P$2") (pinfunction "P$2_P$2") (pintype "passive"))
      (node (ref "PD2") (pin "C") (pinfunction "C_C") (pintype "passive"))
      (node (ref "PIC33") (pin "2") (pinfunction "OUT_2") (pintype "output"))
    )
    (net (code "46") (name "Net-(PJ1-PWR)") (class "Default")
      (node (ref "PD1") (pin "A") (pinfunction "A_A") (pintype "passive"))
      (node (ref "PJ1") (pin "VIN0") (pinfunction "PWR_VIN0") (pintype "bidirectional"))
    )
    (net (code "47") (name "Net-(PL-PadA)") (class "Default")
      (node (ref "PL") (pin "A") (pinfunction "A_A") (pintype "passive"))
      (node (ref "PR1") (pin "1") (pinfunction "1_1") (pintype "passive"))
    )
    (net (code "48") (name "Net-(U1-PB6(XTAL1{slash}TOSC1))") (class "Default")
      (node (ref "Q1") (pin "1") (pinfunction "1_1") (pintype "passive"))
      (node (ref "U1") (pin "7") (pinfunction "PB6(XTAL1/TOSC1)_7") (pintype "bidirectional"))
    )
    (net (code "49") (name "Net-(U1-PB7(XTAL2{slash}TOSC2))") (class "Default")
      (node (ref "Q1") (pin "3") (pinfunction "3_3") (pintype "passive"))
      (node (ref "U1") (pin "8") (pinfunction "PB7(XTAL2/TOSC2)_8") (pintype "bidirectional"))
    )
    (net (code "50") (name "RAW_IV") (class "Default")
      (node (ref "OD1") (pin "C") (pinfunction "C_C") (pintype "passive"))
      (node (ref "OD2") (pin "C") (pinfunction "C_C") (pintype "passive"))
      (node (ref "OD3") (pin "C") (pinfunction "C_C") (pintype "passive"))
      (node (ref "PC1") (pin "+") (pinfunction "+_+") (pintype "passive"))
      (node (ref "PF1") (pin "2") (pinfunction "2_2") (pintype "passive"))
      (node (ref "PIC33") (pin "1") (pinfunction "VIN_1") (pintype "input"))
      (node (ref "XI") (pin "1") (pinfunction "1_1") (pintype "passive"))
      (node (ref "XO") (pin "1") (pinfunction "1_1") (pintype "passive"))
      (node (ref "XO") (pin "3") (pinfunction "1_3") (pintype "passive"))
      (node (ref "XO") (pin "5") (pinfunction "1_5") (pintype "passive"))
    )
    (net (code "51") (name "RESET") (class "Default")
      (node (ref "C2") (pin "1") (pinfunction "1_1") (pintype "passive"))
      (node (ref "R2") (pin "1") (pinfunction "1_1") (pintype "passive"))
      (node (ref "SR") (pin "1") (pinfunction "P_1") (pintype "passive"))
      (node (ref "U1") (pin "29") (pinfunction "PC6(/RESET)_29") (pintype "bidirectional"))
    )
    (net (code "52") (name "RXI") (class "Default")
      (node (ref "PP") (pin "4") (pinfunction "S_4") (pintype "passive"))
      (node (ref "U1") (pin "30") (pinfunction "PD0(RXD)_30") (pintype "bidirectional"))
    )
    (net (code "53") (name "TXO") (class "Default")
      (node (ref "PP") (pin "3") (pinfunction "S_3") (pintype "passive"))
      (node (ref "U1") (pin "31") (pinfunction "PD1(TXD)_31") (pintype "bidirectional"))
    )
    (net (code "54") (name "unconnected-(ENC-CLKOUT-Pad3)") (class "Default")
      (node (ref "ENC") (pin "3") (pinfunction "CLKOUT_3") (pintype "output"))
    )
    (net (code "55") (name "unconnected-(ENC-WOL-Pad5)") (class "Default")
      (node (ref "ENC") (pin "5") (pinfunction "WOL_5") (pintype "output"))
    )
    (net (code "56") (name "unconnected-(PJ1-GND-PadP$4)") (class "Default")
      (node (ref "PJ1") (pin "P$4") (pinfunction "GND_P$4") (pintype "bidirectional"))
    )
    (net (code "57") (name "unconnected-(U$2-PadNC)") (class "Default")
      (node (ref "U$2") (pin "NC") (pinfunction "NC_NC") (pintype "bidirectional"))
    )
    (net (code "58") (name "unconnected-(U$2-PadP5)") (class "Default")
      (node (ref "U$2") (pin "P5") (pinfunction "P5_P5") (pintype "bidirectional"))
    )
    (net (code "59") (name "unconnected-(WIFI-PadGPIO0)") (class "Default")
      (node (ref "WIFI") (pin "GPIO0") (pinfunction "GPIO0_GPIO0") (pintype "bidirectional"))
    )
    (net (code "60") (name "unconnected-(WIFI-PadGPIO2)") (class "Default")
      (node (ref "WIFI") (pin "GPIO2") (pinfunction "GPIO2_GPIO2") (pintype "bidirectional"))
    )
    (net (code "61") (name "unconnected-(WIFI-PadRST)") (class "Default")
      (node (ref "WIFI") (pin "RST") (pinfunction "RST_RST") (pintype "bidirectional"))
    )
  )
)
